# Power_Supplies.net
KiCad netlist of a schematic drawn in Altium Designer
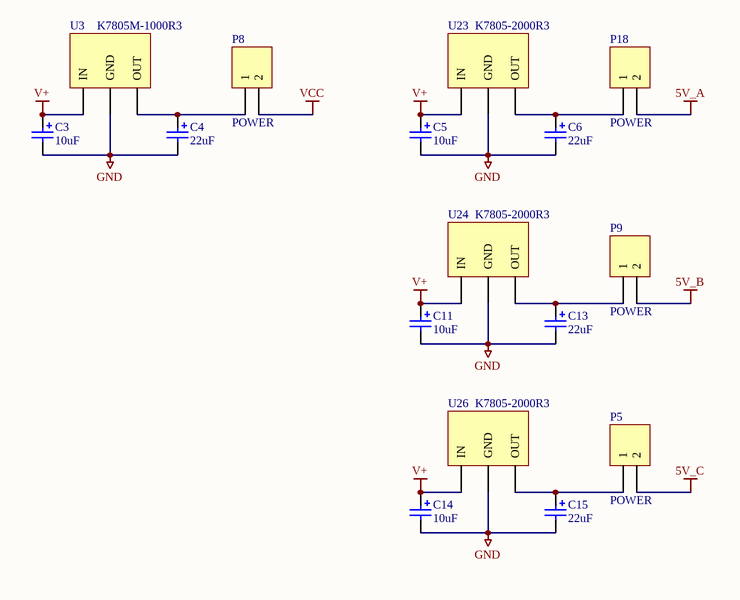
[diagram p0: Power Supplies.SchDoc]

(export (version "E")
  (design (tool "Eeschema 10.0.6"))
  (components
    (comp (ref "C3")
      (value "10uF")
      (footprint "CAPACITOR 6.3x7")
      (description "Polarized Capacitor (Radial)")
      (fields (field (name "LCSC PART NUMBER") "C160183"))
      (libsource (lib "altium-import") (part "root_3_Aluminum 10Dx16Hx5P_"))
    )
    (comp (ref "C4")
      (value "22uF")
      (footprint "CAPACITOR 5x11")
      (description "Polarized Capacitor (Radial)")
      (fields (field (name "LCSC PART NUMBER") "C512951"))
      (libsource (lib "Low Cost Labs") (part "Aluminum 10Dx16Hx5P"))
    )
    (comp (ref "C5")
      (value "10uF")
      (footprint "CAPACITOR 6.3x7")
      (description "Polarized Capacitor (Radial)")
      (fields (field (name "LCSC PART NUMBER") "C160183"))
      (libsource (lib "altium-import") (part "root_3_Aluminum 10Dx16Hx5P_"))
    )
    (comp (ref "C6")
      (value "22uF")
      (footprint "CAPACITOR 5x11")
      (description "Polarized Capacitor (Radial)")
      (fields (field (name "LCSC PART NUMBER") "C512951"))
      (libsource (lib "Low Cost Labs") (part "Aluminum 10Dx16Hx5P"))
    )
    (comp (ref "C11")
      (value "10uF")
      (footprint "CAPACITOR 6.3x7")
      (description "Polarized Capacitor (Radial)")
      (fields (field (name "LCSC PART NUMBER") "C160183"))
      (libsource (lib "altium-import") (part "root_3_Aluminum 10Dx16Hx5P_"))
    )
    (comp (ref "C13")
      (value "22uF")
      (footprint "CAPACITOR 5x11")
      (description "Polarized Capacitor (Radial)")
      (fields (field (name "LCSC PART NUMBER") "C512951"))
      (libsource (lib "Low Cost Labs") (part "Aluminum 10Dx16Hx5P"))
    )
    (comp (ref "C14")
      (value "10uF")
      (footprint "CAPACITOR 6.3x7")
      (description "Polarized Capacitor (Radial)")
      (fields (field (name "LCSC PART NUMBER") "C160183"))
      (libsource (lib "altium-import") (part "root_3_Aluminum 10Dx16Hx5P_"))
    )
    (comp (ref "C15")
      (value "22uF")
      (footprint "CAPACITOR 5x11")
      (description "Polarized Capacitor (Radial)")
      (fields (field (name "LCSC PART NUMBER") "C512951"))
      (libsource (lib "Low Cost Labs") (part "Aluminum 10Dx16Hx5P"))
    )
    (comp (ref "P5")
      (value "POWER")
      (footprint "HEADER 1x2")
      (description "Header, 2-Pin")
      (fields (field (name "PUBLISHER") "Altium Limited"))
      (libsource (lib "XC Tail Light Driver") (part "Header 2"))
    )
    (comp (ref "P8")
      (value "POWER")
      (footprint "HEADER 1x2")
      (description "Header, 2-Pin")
      (fields (field (name "PUBLISHER") "Altium Limited"))
      (libsource (lib "XC Tail Light Driver") (part "Header 2"))
    )
    (comp (ref "P9")
      (value "POWER")
      (footprint "HEADER 1x2")
      (description "Header, 2-Pin")
      (fields (field (name "PUBLISHER") "Altium Limited"))
      (libsource (lib "XC Tail Light Driver") (part "Header 2"))
    )
    (comp (ref "P18")
      (value "POWER")
      (footprint "HEADER 1x2")
      (description "Header, 2-Pin")
      (fields (field (name "PUBLISHER") "Altium Limited"))
      (libsource (lib "XC Tail Light Driver") (part "Header 2"))
    )
    (comp (ref "U3")
      (value "K7805M-1000R3")
      (footprint "K78xxM-1000R3")
      (description "RS_PRO K7805M-1000R3")
      (libsource (lib "907 Power Supply") (part "TRACO 1-2450"))
    )
    (comp (ref "U23")
      (value "K7805-2000R3")
      (footprint "K78xxM-1000R3L")
      (description "RS_PRO K7805-2000R3L")
      (libsource (lib "907 Power Supply") (part "TRACO 1-2450"))
    )
    (comp (ref "U24")
      (value "K7805-2000R3")
      (footprint "K78xxM-1000R3L")
      (description "RS_PRO K7805-2000R3L")
      (libsource (lib "907 Power Supply") (part "TRACO 1-2450"))
    )
    (comp (ref "U26")
      (value "K7805-2000R3")
      (footprint "K78xxM-1000R3L")
      (description "RS_PRO K7805-2000R3L")
      (libsource (lib "907 Power Supply") (part "TRACO 1-2450"))
    )
  )
  (nets
    (net (code "1") (name "5V_A") (class "Default")
      (node (ref "P18") (pin "2") (pinfunction "2_2") (pintype "passive"))
    )
    (net (code "2") (name "5V_B") (class "Default")
      (node (ref "P9") (pin "2") (pinfunction "2_2") (pintype "passive"))
    )
    (net (code "3") (name "5V_C") (class "Default")
      (node (ref "P5") (pin "2") (pinfunction "2_2") (pintype "passive"))
    )
    (net (code "4") (name "GND") (class "Default")
      (node (ref "C11") (pin "2") (pinfunction "2_2") (pintype "passive"))
      (node (ref "C13") (pin "2") (pinfunction "2_2") (pintype "passive"))
      (node (ref "C14") (pin "2") (pinfunction "2_2") (pintype "passive"))
      (node (ref "C15") (pin "2") (pinfunction "2_2") (pintype "passive"))
      (node (ref "C3") (pin "2") (pinfunction "2_2") (pintype "passive"))
      (node (ref "C4") (pin "2") (pinfunction "2_2") (pintype "passive"))
      (node (ref "C5") (pin "2") (pinfunction "2_2") (pintype "passive"))
      (node (ref "C6") (pin "2") (pinfunction "2_2") (pintype "passive"))
      (node (ref "U23") (pin "2") (pinfunction "GND_2") (pintype "passive"))
      (node (ref "U24") (pin "2") (pinfunction "GND_2") (pintype "passive"))
      (node (ref "U26") (pin "2") (pinfunction "GND_2") (pintype "passive"))
      (node (ref "U3") (pin "2") (pinfunction "GND_2") (pintype "passive"))
    )
    (net (code "5") (name "Net-(U3-OUT)") (class "Default")
      (node (ref "C4") (pin "1") (pinfunction "1_1") (pintype "passive"))
      (node (ref "P8") (pin "1") (pinfunction "1_1") (pintype "passive"))
      (node (ref "U3") (pin "3") (pinfunction "OUT_3") (pintype "passive"))
    )
    (net (code "6") (name "Net-(U23-OUT)") (class "Default")
      (node (ref "C6") (pin "1") (pinfunction "1_1") (pintype "passive"))
      (node (ref "P18") (pin "1") (pinfunction "1_1") (pintype "passive"))
      (node (ref "U23") (pin "3") (pinfunction "OUT_3") (pintype "passive"))
    )
    (net (code "7") (name "Net-(U24-OUT)") (class "Default")
      (node (ref "C13") (pin "1") (pinfunction "1_1") (pintype "passive"))
      (node (ref "P9") (pin "1") (pinfunction "1_1") (pintype "passive"))
      (node (ref "U24") (pin "3") (pinfunction "OUT_3") (pintype "passive"))
    )
    (net (code "8") (name "Net-(U26-OUT)") (class "Default")
      (node (ref "C15") (pin "1") (pinfunction "1_1") (pintype "passive"))
      (node (ref "P5") (pin "1") (pinfunction "1_1") (pintype "passive"))
      (node (ref "U26") (pin "3") (pinfunction "OUT_3") (pintype "passive"))
    )
    (net (code "9") (name "V+") (class "Default")
      (node (ref "C11") (pin "1") (pinfunction "1_1") (pintype "passive"))
      (node (ref "C14") (pin "1") (pinfunction "1_1") (pintype "passive"))
      (node (ref "C3") (pin "1") (pinfunction "1_1") (pintype "passive"))
      (node (ref "C5") (pin "1") (pinfunction "1_1") (pintype "passive"))
      (node (ref "U23") (pin "1") (pinfunction "IN_1") (pintype "passive"))
      (node (ref "U24") (pin "1") (pinfunction "IN_1") (pintype "passive"))
      (node (ref "U26") (pin "1") (pinfunction "IN_1") (pintype "passive"))
      (node (ref "U3") (pin "1") (pinfunction "IN_1") (pintype "passive"))
    )
    (net (code "10") (name "VCC") (class "Default")
      (node (ref "P8") (pin "2") (pinfunction "2_2") (pintype "passive"))
    )
  )
)
